# GSM_Antenna.net
KiCad netlist of a schematic drawn in Altium Designer
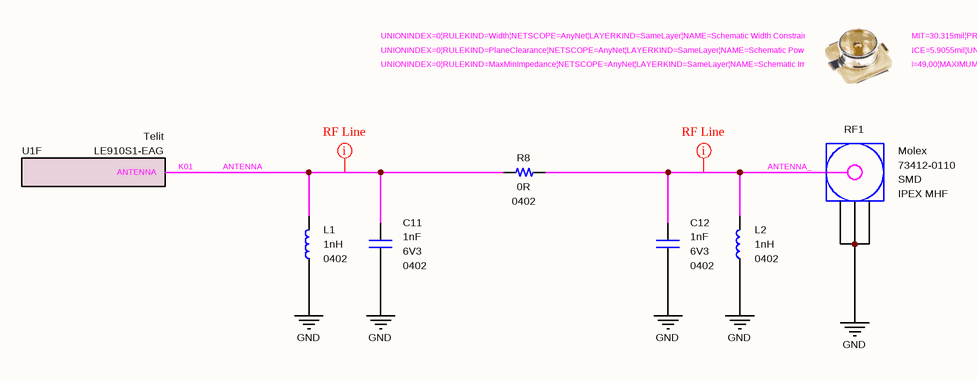
[diagram p0: GSM Antenna.SchDoc]

(export (version "E")
  (design (tool "Eeschema 10.0.6"))
  (components
    (comp (ref "C11")
      (value "1nF")
      (footprint "CAPACITOR_0402")
      (description "Capacitor - 1nF [0402] (Ceramic)")
      (fields
        (field (name "CASE") "0402")
        (field (name "VOLTAGE") "6V3")
        (field (name "MANUFACTURER PART NUMBER") "04026C102MAT2A")
        (field (name "TOLERANCE") "20%")
      )
      (libsource (lib "P101DA_Library") (part "1nF [0402-6V3]"))
    )
    (comp (ref "C12")
      (value "1nF")
      (footprint "CAPACITOR_0402")
      (description "Capacitor - 1nF [0402] (Ceramic)")
      (fields
        (field (name "CASE") "0402")
        (field (name "VOLTAGE") "6V3")
        (field (name "MANUFACTURER PART NUMBER") "04026C102MAT2A")
        (field (name "TOLERANCE") "20%")
      )
      (libsource (lib "P101DA_Library") (part "1nF [0402-6V3]"))
    )
    (comp (ref "L1")
      (value "1nH")
      (footprint "INDUCTOR_0402")
      (description "Fixed Inductor")
      (fields
        (field (name "CASE") "0402")
        (field (name "MANUFACTURER PART NUMBER") "LQG15HN1N0S02D")
        (field (name "TOLERANCE") "0.3 nH")
      )
      (libsource (lib "P101DA_Library") (part "1nH [0402]"))
    )
    (comp (ref "L2")
      (value "1nH")
      (footprint "INDUCTOR_0402")
      (description "Fixed Inductor")
      (fields
        (field (name "CASE") "0402")
        (field (name "MANUFACTURER PART NUMBER") "LQG15HN1N0S02D")
        (field (name "TOLERANCE") "0.3 nH")
      )
      (libsource (lib "P101DA_Library") (part "1nH [0402]"))
    )
    (comp (ref "R8")
      (value "0R")
      (footprint "RESISTOR_0402")
      (description "Thick Film Resistors - SMD 1/16 W 0 Ohms")
      (fields (field (name "CASE") "0402") (field (name "MANUFACTURER PART NUMBER") "CRCW04020000Z0ED"))
      (libsource (lib "P101DA_Library") (part "0R"))
    )
    (comp (ref "RF1")
      (value "~")
      (footprint "Connector_IPEX")
      (description "MOLEX   73412-0110   RF COAXIAL, MICROCOAXIAL, JACK, 50OHM")
      (fields
        (field (name "CONNECTOR TYPE") "IPEX MHF")
        (field (name "CASE") "SMD")
        (field (name "MANUFACTURER PART NUMBER") "73412-0110")
        (field (name "MANUFACTURER NAME") "Molex")
      )
      (libsource (lib "P101DA_Library") (part "IPEX MHF Connector"))
    )
    (comp (ref "U1")
      (value "LE910S1-EAG LTE GSM Module")
      (footprint "LE910 GSM Modem")
      (description "Telit LE910S1-EAG GPRS/GNSS Module")
      (fields
        (field (name "MANUFACTURER PART NUMBER") "LE910S1-EAG")
        (field (name "MANUFACTURER NAME") "Telit")
      )
      (libsource (lib "P101DA_Library") (part "IC - LE910S1-EAG"))
    )
  )
  (nets
    (net (code "1") (name "/ANTENNA") (class "Default")
      (node (ref "C11") (pin "2") (pinfunction "2_2") (pintype "passive"))
      (node (ref "L1") (pin "2") (pinfunction "2_2") (pintype "passive"))
      (node (ref "R8") (pin "2") (pinfunction "2_2") (pintype "passive"))
      (node (ref "U1") (pin "K01") (pinfunction "ANTENNA_K01") (pintype "passive"))
    )
    (net (code "2") (name "/ANTENNA_") (class "Default")
      (node (ref "C12") (pin "2") (pinfunction "2_2") (pintype "passive"))
      (node (ref "L2") (pin "2") (pinfunction "2_2") (pintype "passive"))
      (node (ref "R8") (pin "1") (pinfunction "1_1") (pintype "passive"))
      (node (ref "RF1") (pin "1") (pinfunction "Signal_1") (pintype "passive"))
    )
    (net (code "3") (name "GND") (class "Default")
      (node (ref "C11") (pin "1") (pinfunction "1_1") (pintype "passive"))
      (node (ref "C12") (pin "1") (pinfunction "1_1") (pintype "passive"))
      (node (ref "L1") (pin "1") (pinfunction "1_1") (pintype "passive"))
      (node (ref "L2") (pin "1") (pinfunction "1_1") (pintype "passive"))
      (node (ref "RF1") (pin "2") (pinfunction "GND_2") (pintype "passive"))
      (node (ref "RF1") (pin "3") (pinfunction "GND_3") (pintype "passive"))
      (node (ref "RF1") (pin "4") (pinfunction "GND_4") (pintype "passive"))
    )
  )
)
